# eeprom.net
KiCad netlist of a schematic drawn in Altium Designer
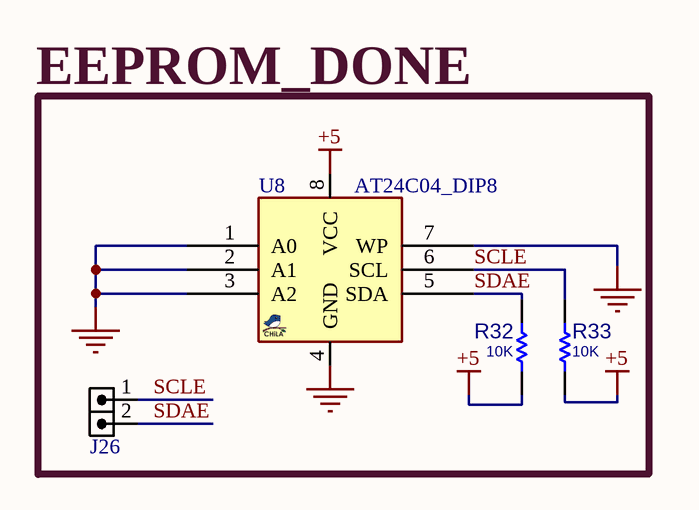
[diagram p0: eeprom.SchDoc]

(export (version "E")
  (design (tool "Eeschema 10.0.6"))
  (components
    (comp (ref "J26")
      (value "HDRM2")
      (footprint "HDR_M_1X2")
      (description "CONN, HEADER, Male, pitch: 2.54mm, 2POS")
      (libsource (lib "conn_header_2.54mm_st") (part "HDR_M_1X2"))
    )
    (comp (ref "R32")
      (value "10K")
      (footprint "R025W_AX04")
      (description "RESISTOR, THD")
      (fields (field (name "MANF_P#") "RK73H1ETTP4701F") (field (name "MANF") "KOA SPEER"))
      (libsource (lib "passive_thd") (part "RES_THD"))
    )
    (comp (ref "R33")
      (value "10K")
      (footprint "R025W_AX04")
      (description "RESISTOR, THD")
      (fields (field (name "MANF_P#") "RK73H1ETTP4701F") (field (name "MANF") "KOA SPEER"))
      (libsource (lib "passive_thd") (part "RES_THD"))
    )
    (comp (ref "U8")
      (value "AT24C04_DIP8")
      (footprint "DIP_8")
      (libsource (lib "memory_eeprom_I2C") (part "EEPROM_I2C_AT24C04_DIP8"))
    )
  )
  (nets
    (net (code "1") (name "+5") (class "Default")
      (node (ref "R32") (pin "2") (pinfunction "2_2") (pintype "passive"))
      (node (ref "R33") (pin "2") (pinfunction "2_2") (pintype "passive"))
      (node (ref "U8") (pin "8") (pinfunction "VCC_8") (pintype "passive"))
    )
    (net (code "2") (name "/SCLE") (class "Default")
      (node (ref "J26") (pin "1") (pinfunction "1_1") (pintype "passive"))
      (node (ref "R33") (pin "1") (pinfunction "1_1") (pintype "passive"))
      (node (ref "U8") (pin "6") (pinfunction "SCL_6") (pintype "passive"))
    )
    (net (code "3") (name "/SDAE") (class "Default")
      (node (ref "J26") (pin "2") (pinfunction "2_2") (pintype "passive"))
      (node (ref "R32") (pin "1") (pinfunction "1_1") (pintype "passive"))
      (node (ref "U8") (pin "5") (pinfunction "SDA_5") (pintype "passive"))
    )
    (net (code "4") (name "GND") (class "Default")
      (node (ref "U8") (pin "1") (pinfunction "A0_1") (pintype "passive"))
      (node (ref "U8") (pin "2") (pinfunction "A1_2") (pintype "passive"))
      (node (ref "U8") (pin "3") (pinfunction "A2_3") (pintype "passive"))
      (node (ref "U8") (pin "4") (pinfunction "GND_4") (pintype "passive"))
      (node (ref "U8") (pin "7") (pinfunction "WP_7") (pintype "passive"))
    )
  )
)
